# DIDV_-_Expansao_05.net
KiCad netlist of a schematic drawn in EAGLE
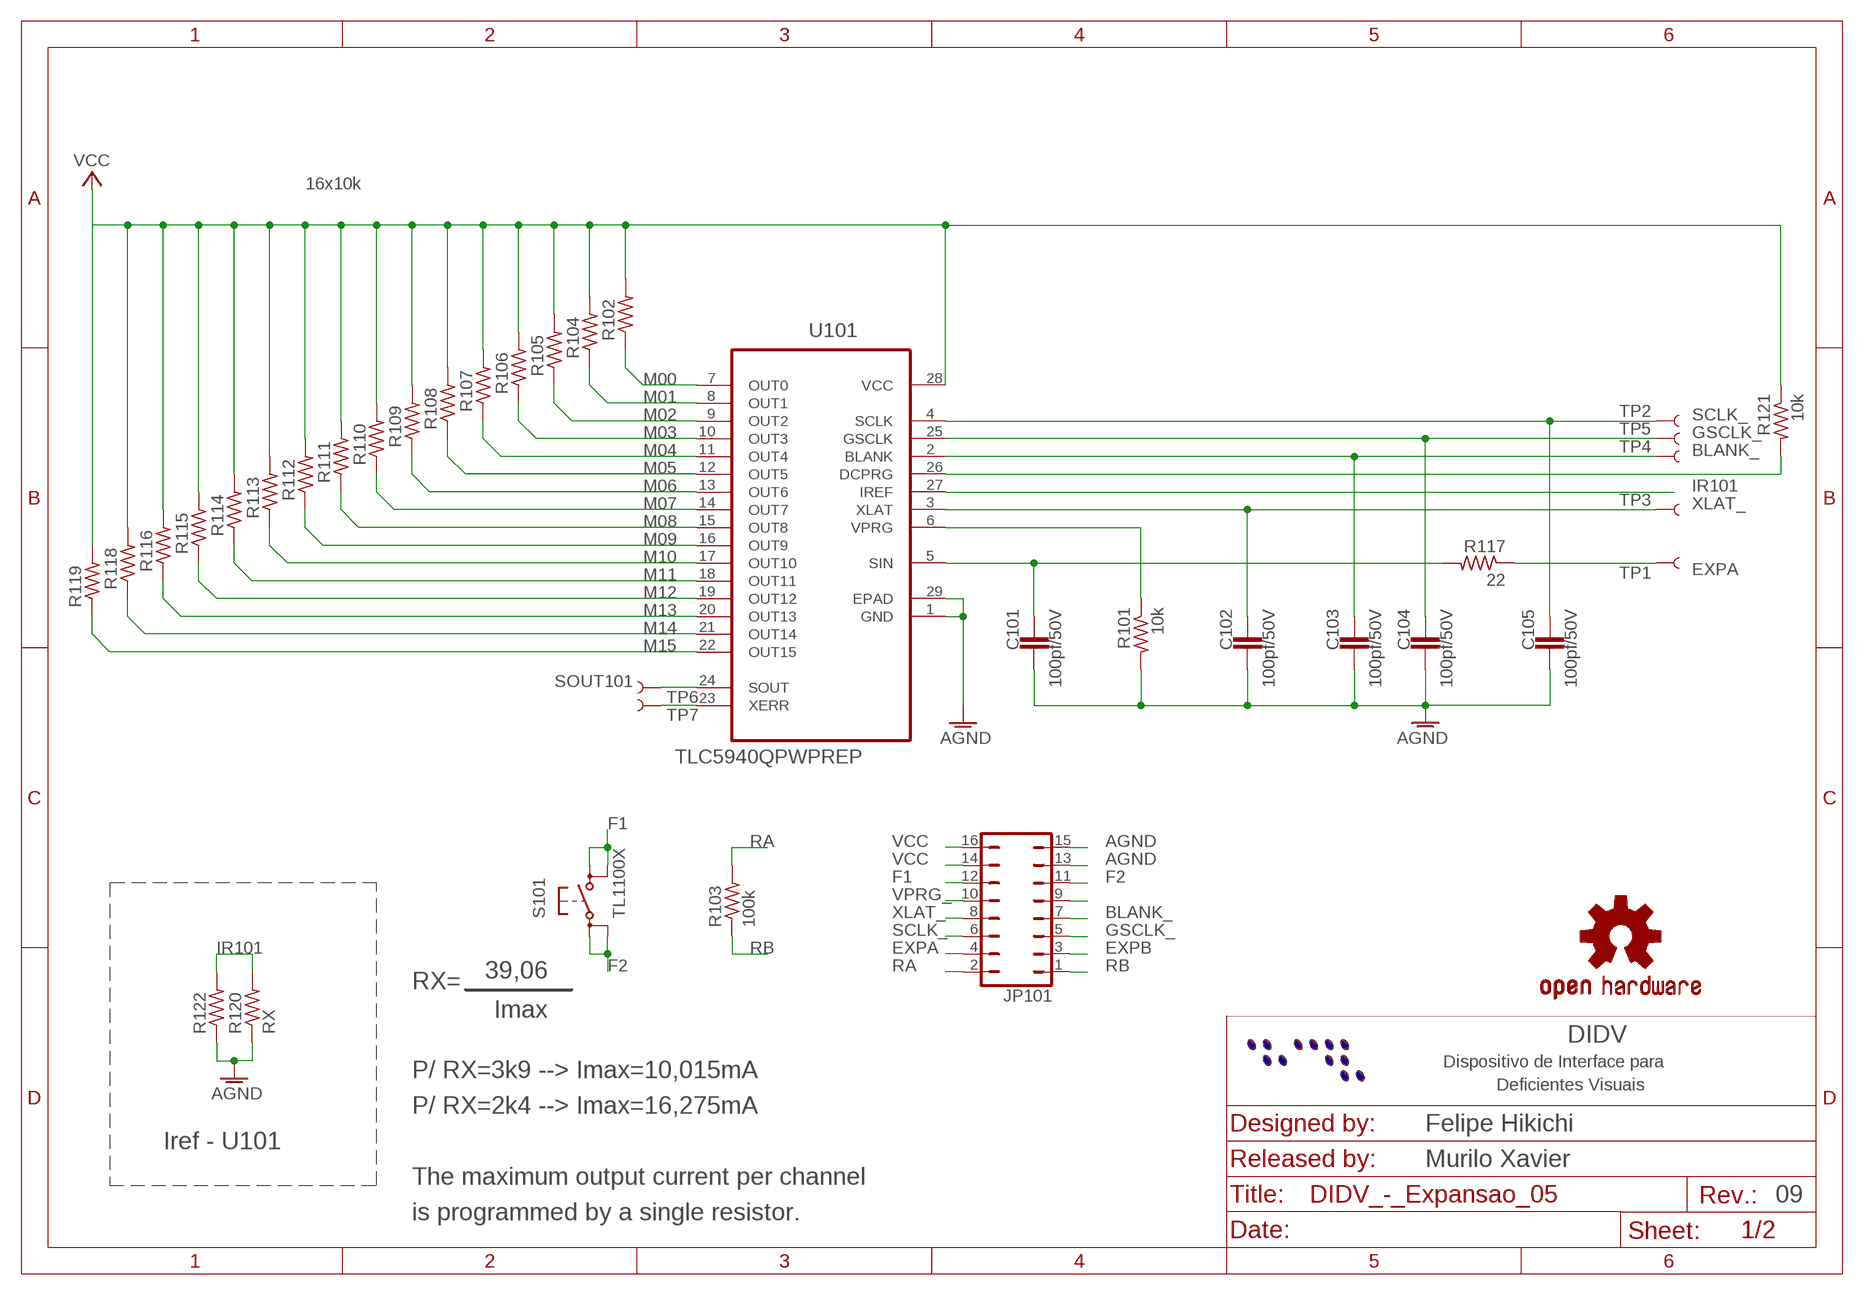
[diagram p0: schematic, sheet 1]
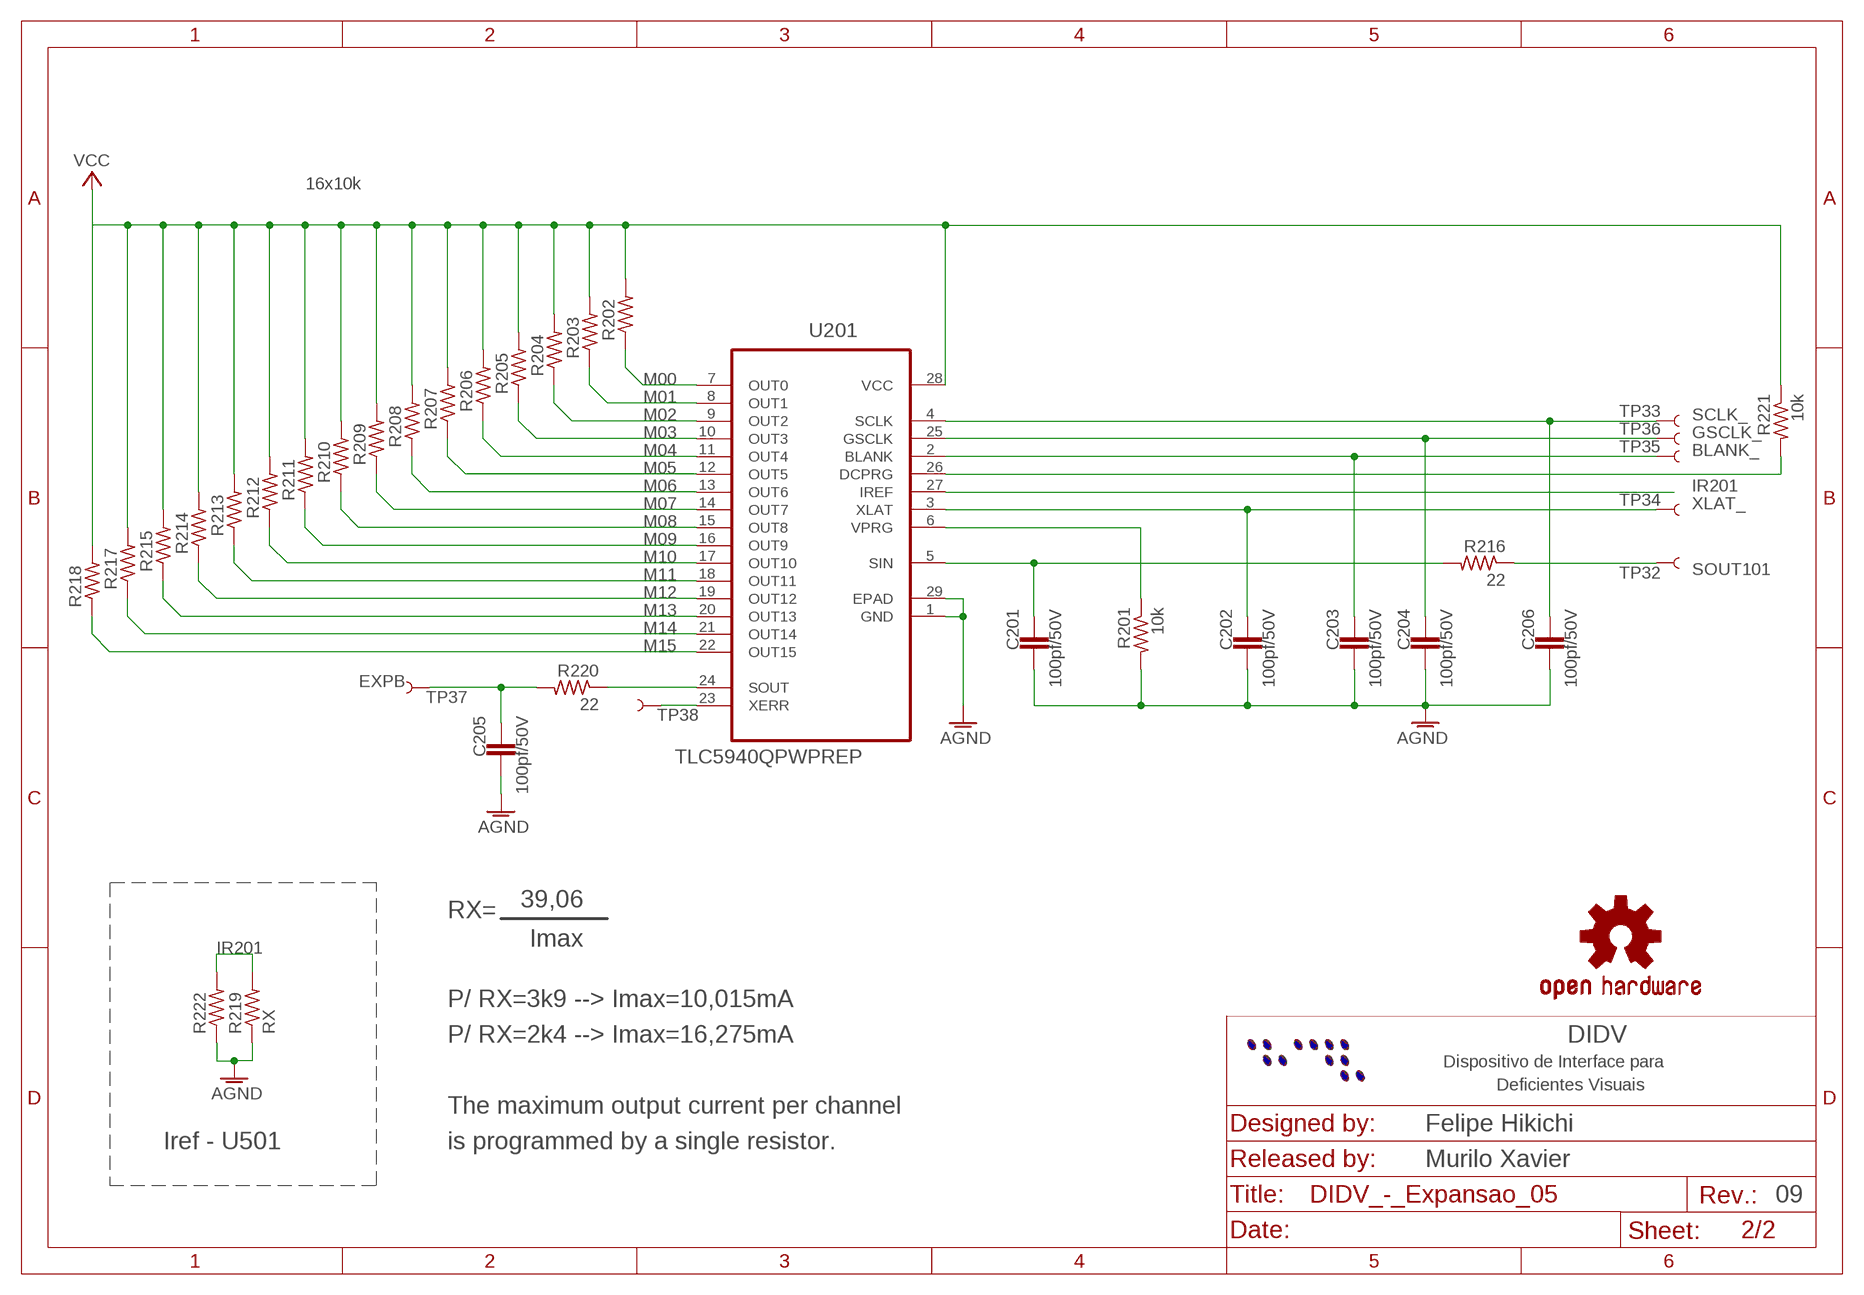
[diagram p1: schematic, sheet 2]

(export (version "E")
  (design (tool "Eeschema 10.0.6"))
  (components
    (comp (ref "C101")
      (value "100pf/50V")
      (footprint "eagle-import:C0603K")
      (libsource (lib "eagle-import") (part "C-EUC0603K"))
    )
    (comp (ref "C102")
      (value "100pf/50V")
      (footprint "eagle-import:C0603K")
      (libsource (lib "eagle-import") (part "C-EUC0603K"))
    )
    (comp (ref "C103")
      (value "100pf/50V")
      (footprint "eagle-import:C0603K")
      (libsource (lib "eagle-import") (part "C-EUC0603K"))
    )
    (comp (ref "C104")
      (value "100pf/50V")
      (footprint "eagle-import:C0603K")
      (libsource (lib "eagle-import") (part "C-EUC0603K"))
    )
    (comp (ref "C105")
      (value "100pf/50V")
      (footprint "eagle-import:C0603K")
      (libsource (lib "eagle-import") (part "C-EUC0603K"))
    )
    (comp (ref "JP101")
      (value "JP8Q")
      (footprint "eagle-import:JP8Q")
      (libsource (lib "eagle-import") (part "JP8Q"))
    )
    (comp (ref "LOGO101")
      (value "OSHW-LOGOM")
      (footprint "eagle-import:OSHW-LOGO-M")
      (libsource (lib "eagle-import") (part "OSHW-LOGOM"))
    )
    (comp (ref "R101")
      (value "10k")
      (footprint "eagle-import:R0603")
      (libsource (lib "eagle-import") (part "R-US_R0603"))
    )
    (comp (ref "R102")
      (value "R-US_R0805")
      (footprint "eagle-import:R0805")
      (libsource (lib "eagle-import") (part "R-US_R0805"))
    )
    (comp (ref "R103")
      (value "100k")
      (footprint "eagle-import:R0805")
      (libsource (lib "eagle-import") (part "R-US_R0805"))
    )
    (comp (ref "R104")
      (value "R-US_R0805")
      (footprint "eagle-import:R0805")
      (libsource (lib "eagle-import") (part "R-US_R0805"))
    )
    (comp (ref "R105")
      (value "R-US_R0805")
      (footprint "eagle-import:R0805")
      (libsource (lib "eagle-import") (part "R-US_R0805"))
    )
    (comp (ref "R106")
      (value "R-US_R0805")
      (footprint "eagle-import:R0805")
      (libsource (lib "eagle-import") (part "R-US_R0805"))
    )
    (comp (ref "R107")
      (value "R-US_R0805")
      (footprint "eagle-import:R0805")
      (libsource (lib "eagle-import") (part "R-US_R0805"))
    )
    (comp (ref "R108")
      (value "R-US_R0805")
      (footprint "eagle-import:R0805")
      (libsource (lib "eagle-import") (part "R-US_R0805"))
    )
    (comp (ref "R109")
      (value "R-US_R0805")
      (footprint "eagle-import:R0805")
      (libsource (lib "eagle-import") (part "R-US_R0805"))
    )
    (comp (ref "R110")
      (value "R-US_R0805")
      (footprint "eagle-import:R0805")
      (libsource (lib "eagle-import") (part "R-US_R0805"))
    )
    (comp (ref "R111")
      (value "R-US_R0805")
      (footprint "eagle-import:R0805")
      (libsource (lib "eagle-import") (part "R-US_R0805"))
    )
    (comp (ref "R112")
      (value "R-US_R0805")
      (footprint "eagle-import:R0805")
      (libsource (lib "eagle-import") (part "R-US_R0805"))
    )
    (comp (ref "R113")
      (value "R-US_R0805")
      (footprint "eagle-import:R0805")
      (libsource (lib "eagle-import") (part "R-US_R0805"))
    )
    (comp (ref "R114")
      (value "R-US_R0805")
      (footprint "eagle-import:R0805")
      (libsource (lib "eagle-import") (part "R-US_R0805"))
    )
    (comp (ref "R115")
      (value "R-US_R0805")
      (footprint "eagle-import:R0805")
      (libsource (lib "eagle-import") (part "R-US_R0805"))
    )
    (comp (ref "R116")
      (value "R-US_R0805")
      (footprint "eagle-import:R0805")
      (libsource (lib "eagle-import") (part "R-US_R0805"))
    )
    (comp (ref "R117")
      (value "22")
      (footprint "eagle-import:R0603")
      (libsource (lib "eagle-import") (part "R-US_R0603"))
    )
    (comp (ref "R118")
      (value "R-US_R0805")
      (footprint "eagle-import:R0805")
      (libsource (lib "eagle-import") (part "R-US_R0805"))
    )
    (comp (ref "R119")
      (value "R-US_R0805")
      (footprint "eagle-import:R0805")
      (libsource (lib "eagle-import") (part "R-US_R0805"))
    )
    (comp (ref "R120")
      (value "RX")
      (footprint "eagle-import:R0805")
      (libsource (lib "eagle-import") (part "R-US_R0805"))
    )
    (comp (ref "R121")
      (value "10k")
      (footprint "eagle-import:R0603")
      (libsource (lib "eagle-import") (part "R-US_R0603"))
    )
    (comp (ref "R122")
      (value "R-US_R0805")
      (footprint "eagle-import:R0805")
      (libsource (lib "eagle-import") (part "R-US_R0805"))
    )
    (comp (ref "S101")
      (value "TL1100X")
      (footprint "eagle-import:TL1100X")
      (libsource (lib "eagle-import") (part "TL1100X"))
    )
    (comp (ref "TP1")
      (value "TEST-POINT3X4")
      (footprint "eagle-import:PAD.03X.04")
      (libsource (lib "eagle-import") (part "TEST-POINT3X4"))
    )
    (comp (ref "TP2")
      (value "TEST-POINT3X4")
      (footprint "eagle-import:PAD.03X.04")
      (libsource (lib "eagle-import") (part "TEST-POINT3X4"))
    )
    (comp (ref "TP3")
      (value "TEST-POINT3X4")
      (footprint "eagle-import:PAD.03X.04")
      (libsource (lib "eagle-import") (part "TEST-POINT3X4"))
    )
    (comp (ref "TP4")
      (value "TEST-POINT3X4")
      (footprint "eagle-import:PAD.03X.04")
      (libsource (lib "eagle-import") (part "TEST-POINT3X4"))
    )
    (comp (ref "TP5")
      (value "TEST-POINT3X4")
      (footprint "eagle-import:PAD.03X.04")
      (libsource (lib "eagle-import") (part "TEST-POINT3X4"))
    )
    (comp (ref "TP6")
      (value "TEST-POINT3X4")
      (footprint "eagle-import:PAD.03X.04")
      (libsource (lib "eagle-import") (part "TEST-POINT3X4"))
    )
    (comp (ref "TP7")
      (value "TEST-POINT3X4")
      (footprint "eagle-import:PAD.03X.04")
      (libsource (lib "eagle-import") (part "TEST-POINT3X4"))
    )
    (comp (ref "U101")
      (value "TLC5940QPWPREP")
      (footprint "eagle-import:SOP65P640X120-29N")
      (libsource (lib "eagle-import") (part "TLC5940QPWPREP"))
    )
    (comp (ref "C201")
      (value "100pf/50V")
      (footprint "eagle-import:C0603K")
      (libsource (lib "eagle-import") (part "C-EUC0603K"))
    )
    (comp (ref "C202")
      (value "100pf/50V")
      (footprint "eagle-import:C0603K")
      (libsource (lib "eagle-import") (part "C-EUC0603K"))
    )
    (comp (ref "C203")
      (value "100pf/50V")
      (footprint "eagle-import:C0603K")
      (libsource (lib "eagle-import") (part "C-EUC0603K"))
    )
    (comp (ref "C204")
      (value "100pf/50V")
      (footprint "eagle-import:C0603K")
      (libsource (lib "eagle-import") (part "C-EUC0603K"))
    )
    (comp (ref "C205")
      (value "100pf/50V")
      (footprint "eagle-import:C0603K")
      (libsource (lib "eagle-import") (part "C-EUC0603K"))
    )
    (comp (ref "C206")
      (value "100pf/50V")
      (footprint "eagle-import:C0603K")
      (libsource (lib "eagle-import") (part "C-EUC0603K"))
    )
    (comp (ref "LOGO201")
      (value "OSHW-LOGOM")
      (footprint "eagle-import:OSHW-LOGO-M")
      (libsource (lib "eagle-import") (part "OSHW-LOGOM"))
    )
    (comp (ref "R201")
      (value "10k")
      (footprint "eagle-import:R0603")
      (libsource (lib "eagle-import") (part "R-US_R0603"))
    )
    (comp (ref "R202")
      (value "R-US_R0805")
      (footprint "eagle-import:R0805")
      (libsource (lib "eagle-import") (part "R-US_R0805"))
    )
    (comp (ref "R203")
      (value "R-US_R0805")
      (footprint "eagle-import:R0805")
      (libsource (lib "eagle-import") (part "R-US_R0805"))
    )
    (comp (ref "R204")
      (value "R-US_R0805")
      (footprint "eagle-import:R0805")
      (libsource (lib "eagle-import") (part "R-US_R0805"))
    )
    (comp (ref "R205")
      (value "R-US_R0805")
      (footprint "eagle-import:R0805")
      (libsource (lib "eagle-import") (part "R-US_R0805"))
    )
    (comp (ref "R206")
      (value "R-US_R0805")
      (footprint "eagle-import:R0805")
      (libsource (lib "eagle-import") (part "R-US_R0805"))
    )
    (comp (ref "R207")
      (value "R-US_R0805")
      (footprint "eagle-import:R0805")
      (libsource (lib "eagle-import") (part "R-US_R0805"))
    )
    (comp (ref "R208")
      (value "R-US_R0805")
      (footprint "eagle-import:R0805")
      (libsource (lib "eagle-import") (part "R-US_R0805"))
    )
    (comp (ref "R209")
      (value "R-US_R0805")
      (footprint "eagle-import:R0805")
      (libsource (lib "eagle-import") (part "R-US_R0805"))
    )
    (comp (ref "R210")
      (value "R-US_R0805")
      (footprint "eagle-import:R0805")
      (libsource (lib "eagle-import") (part "R-US_R0805"))
    )
    (comp (ref "R211")
      (value "R-US_R0805")
      (footprint "eagle-import:R0805")
      (libsource (lib "eagle-import") (part "R-US_R0805"))
    )
    (comp (ref "R212")
      (value "R-US_R0805")
      (footprint "eagle-import:R0805")
      (libsource (lib "eagle-import") (part "R-US_R0805"))
    )
    (comp (ref "R213")
      (value "R-US_R0805")
      (footprint "eagle-import:R0805")
      (libsource (lib "eagle-import") (part "R-US_R0805"))
    )
    (comp (ref "R214")
      (value "R-US_R0805")
      (footprint "eagle-import:R0805")
      (libsource (lib "eagle-import") (part "R-US_R0805"))
    )
    (comp (ref "R215")
      (value "R-US_R0805")
      (footprint "eagle-import:R0805")
      (libsource (lib "eagle-import") (part "R-US_R0805"))
    )
    (comp (ref "R216")
      (value "22")
      (footprint "eagle-import:R0603")
      (libsource (lib "eagle-import") (part "R-US_R0603"))
    )
    (comp (ref "R217")
      (value "R-US_R0805")
      (footprint "eagle-import:R0805")
      (libsource (lib "eagle-import") (part "R-US_R0805"))
    )
    (comp (ref "R218")
      (value "R-US_R0805")
      (footprint "eagle-import:R0805")
      (libsource (lib "eagle-import") (part "R-US_R0805"))
    )
    (comp (ref "R219")
      (value "RX")
      (footprint "eagle-import:R0805")
      (libsource (lib "eagle-import") (part "R-US_R0805"))
    )
    (comp (ref "R220")
      (value "22")
      (footprint "eagle-import:R0603")
      (libsource (lib "eagle-import") (part "R-US_R0603"))
    )
    (comp (ref "R221")
      (value "10k")
      (footprint "eagle-import:R0603")
      (libsource (lib "eagle-import") (part "R-US_R0603"))
    )
    (comp (ref "R222")
      (value "R-US_R0805")
      (footprint "eagle-import:R0805")
      (libsource (lib "eagle-import") (part "R-US_R0805"))
    )
    (comp (ref "TP32")
      (value "TEST-POINT3X4")
      (footprint "eagle-import:PAD.03X.04")
      (libsource (lib "eagle-import") (part "TEST-POINT3X4"))
    )
    (comp (ref "TP33")
      (value "TEST-POINT3X4")
      (footprint "eagle-import:PAD.03X.04")
      (libsource (lib "eagle-import") (part "TEST-POINT3X4"))
    )
    (comp (ref "TP34")
      (value "TEST-POINT3X4")
      (footprint "eagle-import:PAD.03X.04")
      (libsource (lib "eagle-import") (part "TEST-POINT3X4"))
    )
    (comp (ref "TP35")
      (value "TEST-POINT3X4")
      (footprint "eagle-import:PAD.03X.04")
      (libsource (lib "eagle-import") (part "TEST-POINT3X4"))
    )
    (comp (ref "TP36")
      (value "TEST-POINT3X4")
      (footprint "eagle-import:PAD.03X.04")
      (libsource (lib "eagle-import") (part "TEST-POINT3X4"))
    )
    (comp (ref "TP37")
      (value "TEST-POINT3X4")
      (footprint "eagle-import:PAD.03X.04")
      (libsource (lib "eagle-import") (part "TEST-POINT3X4"))
    )
    (comp (ref "TP38")
      (value "TEST-POINT3X4")
      (footprint "eagle-import:PAD.03X.04")
      (libsource (lib "eagle-import") (part "TEST-POINT3X4"))
    )
    (comp (ref "U201")
      (value "TLC5940QPWPREP")
      (footprint "eagle-import:SOP65P640X120-29N")
      (libsource (lib "eagle-import") (part "TLC5940QPWPREP"))
    )
  )
  (nets
    (net (code "1") (name "AGND") (class "Default")
      (node (ref "C101") (pin "1") (pinfunction "1_1") (pintype "passive"))
      (node (ref "C102") (pin "1") (pinfunction "1_1") (pintype "passive"))
      (node (ref "C103") (pin "1") (pinfunction "1_1") (pintype "passive"))
      (node (ref "C104") (pin "1") (pinfunction "1_1") (pintype "passive"))
      (node (ref "C105") (pin "1") (pinfunction "1_1") (pintype "passive"))
      (node (ref "C201") (pin "1") (pinfunction "1_1") (pintype "passive"))
      (node (ref "C202") (pin "1") (pinfunction "1_1") (pintype "passive"))
      (node (ref "C203") (pin "1") (pinfunction "1_1") (pintype "passive"))
      (node (ref "C204") (pin "1") (pinfunction "1_1") (pintype "passive"))
      (node (ref "C205") (pin "1") (pinfunction "1_1") (pintype "passive"))
      (node (ref "C206") (pin "1") (pinfunction "1_1") (pintype "passive"))
      (node (ref "JP101") (pin "13") (pinfunction "13_13") (pintype "passive"))
      (node (ref "JP101") (pin "15") (pinfunction "15_15") (pintype "passive"))
      (node (ref "R101") (pin "2") (pinfunction "2_2") (pintype "passive"))
      (node (ref "R120") (pin "1") (pinfunction "1_1") (pintype "passive"))
      (node (ref "R122") (pin "1") (pinfunction "1_1") (pintype "passive"))
      (node (ref "R201") (pin "2") (pinfunction "2_2") (pintype "passive"))
      (node (ref "R219") (pin "1") (pinfunction "1_1") (pintype "passive"))
      (node (ref "R222") (pin "1") (pinfunction "1_1") (pintype "passive"))
      (node (ref "U101") (pin "1") (pinfunction "GND_1") (pintype "passive"))
      (node (ref "U101") (pin "29") (pinfunction "EPAD_29") (pintype "passive"))
      (node (ref "U201") (pin "1") (pinfunction "GND_1") (pintype "passive"))
      (node (ref "U201") (pin "29") (pinfunction "EPAD_29") (pintype "passive"))
    )
    (net (code "2") (name "BLANK_") (class "Default")
      (node (ref "C103") (pin "2") (pinfunction "2_2") (pintype "passive"))
      (node (ref "C203") (pin "2") (pinfunction "2_2") (pintype "passive"))
      (node (ref "JP101") (pin "7") (pinfunction "7_7") (pintype "passive"))
      (node (ref "TP35") (pin "P$1") (pinfunction "1_P$1") (pintype "bidirectional"))
      (node (ref "TP4") (pin "P$1") (pinfunction "1_P$1") (pintype "bidirectional"))
      (node (ref "U101") (pin "2") (pinfunction "BLANK_2") (pintype "input"))
      (node (ref "U201") (pin "2") (pinfunction "BLANK_2") (pintype "input"))
    )
    (net (code "3") (name "EXPA") (class "Default")
      (node (ref "JP101") (pin "4") (pinfunction "4_4") (pintype "passive"))
      (node (ref "R117") (pin "1") (pinfunction "1_1") (pintype "passive"))
      (node (ref "TP1") (pin "P$1") (pinfunction "1_P$1") (pintype "bidirectional"))
    )
    (net (code "4") (name "EXPB") (class "Default")
      (node (ref "C205") (pin "2") (pinfunction "2_2") (pintype "passive"))
      (node (ref "JP101") (pin "3") (pinfunction "3_3") (pintype "passive"))
      (node (ref "R220") (pin "2") (pinfunction "2_2") (pintype "passive"))
      (node (ref "TP37") (pin "P$1") (pinfunction "1_P$1") (pintype "bidirectional"))
    )
    (net (code "5") (name "F1") (class "Default")
      (node (ref "JP101") (pin "12") (pinfunction "12_12") (pintype "passive"))
      (node (ref "S101") (pin "3") (pinfunction "S_3") (pintype "passive"))
      (node (ref "S101") (pin "4") (pinfunction "S1_4") (pintype "passive"))
    )
    (net (code "6") (name "F2") (class "Default")
      (node (ref "JP101") (pin "11") (pinfunction "11_11") (pintype "passive"))
      (node (ref "S101") (pin "1") (pinfunction "P_1") (pintype "passive"))
      (node (ref "S101") (pin "2") (pinfunction "P1_2") (pintype "passive"))
    )
    (net (code "7") (name "GSCLK_") (class "Default")
      (node (ref "C104") (pin "2") (pinfunction "2_2") (pintype "passive"))
      (node (ref "C204") (pin "2") (pinfunction "2_2") (pintype "passive"))
      (node (ref "JP101") (pin "5") (pinfunction "5_5") (pintype "passive"))
      (node (ref "TP36") (pin "P$1") (pinfunction "1_P$1") (pintype "bidirectional"))
      (node (ref "TP5") (pin "P$1") (pinfunction "1_P$1") (pintype "bidirectional"))
      (node (ref "U101") (pin "25") (pinfunction "GSCLK_25") (pintype "input"))
      (node (ref "U201") (pin "25") (pinfunction "GSCLK_25") (pintype "input"))
    )
    (net (code "8") (name "IR101") (class "Default")
      (node (ref "R120") (pin "2") (pinfunction "2_2") (pintype "passive"))
      (node (ref "R122") (pin "2") (pinfunction "2_2") (pintype "passive"))
      (node (ref "U101") (pin "27") (pinfunction "IREF_27") (pintype "input"))
    )
    (net (code "9") (name "IR201") (class "Default")
      (node (ref "R219") (pin "2") (pinfunction "2_2") (pintype "passive"))
      (node (ref "R222") (pin "2") (pinfunction "2_2") (pintype "passive"))
      (node (ref "U201") (pin "27") (pinfunction "IREF_27") (pintype "input"))
    )
    (net (code "10") (name "M00") (class "Default")
      (node (ref "R102") (pin "1") (pinfunction "1_1") (pintype "passive"))
      (node (ref "R202") (pin "1") (pinfunction "1_1") (pintype "passive"))
      (node (ref "U101") (pin "7") (pinfunction "OUT0_7") (pintype "output"))
      (node (ref "U201") (pin "7") (pinfunction "OUT0_7") (pintype "output"))
    )
    (net (code "11") (name "M01") (class "Default")
      (node (ref "R104") (pin "1") (pinfunction "1_1") (pintype "passive"))
      (node (ref "R203") (pin "1") (pinfunction "1_1") (pintype "passive"))
      (node (ref "U101") (pin "8") (pinfunction "OUT1_8") (pintype "output"))
      (node (ref "U201") (pin "8") (pinfunction "OUT1_8") (pintype "output"))
    )
    (net (code "12") (name "M02") (class "Default")
      (node (ref "R105") (pin "1") (pinfunction "1_1") (pintype "passive"))
      (node (ref "R204") (pin "1") (pinfunction "1_1") (pintype "passive"))
      (node (ref "U101") (pin "9") (pinfunction "OUT2_9") (pintype "output"))
      (node (ref "U201") (pin "9") (pinfunction "OUT2_9") (pintype "output"))
    )
    (net (code "13") (name "M03") (class "Default")
      (node (ref "R106") (pin "1") (pinfunction "1_1") (pintype "passive"))
      (node (ref "R205") (pin "1") (pinfunction "1_1") (pintype "passive"))
      (node (ref "U101") (pin "10") (pinfunction "OUT3_10") (pintype "output"))
      (node (ref "U201") (pin "10") (pinfunction "OUT3_10") (pintype "output"))
    )
    (net (code "14") (name "M04") (class "Default")
      (node (ref "R107") (pin "1") (pinfunction "1_1") (pintype "passive"))
      (node (ref "R206") (pin "1") (pinfunction "1_1") (pintype "passive"))
      (node (ref "U101") (pin "11") (pinfunction "OUT4_11") (pintype "output"))
      (node (ref "U201") (pin "11") (pinfunction "OUT4_11") (pintype "output"))
    )
    (net (code "15") (name "M05") (class "Default")
      (node (ref "R108") (pin "1") (pinfunction "1_1") (pintype "passive"))
      (node (ref "R207") (pin "1") (pinfunction "1_1") (pintype "passive"))
      (node (ref "U101") (pin "12") (pinfunction "OUT5_12") (pintype "output"))
      (node (ref "U201") (pin "12") (pinfunction "OUT5_12") (pintype "output"))
    )
    (net (code "16") (name "M06") (class "Default")
      (node (ref "R109") (pin "1") (pinfunction "1_1") (pintype "passive"))
      (node (ref "R208") (pin "1") (pinfunction "1_1") (pintype "passive"))
      (node (ref "U101") (pin "13") (pinfunction "OUT6_13") (pintype "output"))
      (node (ref "U201") (pin "13") (pinfunction "OUT6_13") (pintype "output"))
    )
    (net (code "17") (name "M07") (class "Default")
      (node (ref "R110") (pin "1") (pinfunction "1_1") (pintype "passive"))
      (node (ref "R209") (pin "1") (pinfunction "1_1") (pintype "passive"))
      (node (ref "U101") (pin "14") (pinfunction "OUT7_14") (pintype "output"))
      (node (ref "U201") (pin "14") (pinfunction "OUT7_14") (pintype "output"))
    )
    (net (code "18") (name "M08") (class "Default")
      (node (ref "R111") (pin "1") (pinfunction "1_1") (pintype "passive"))
      (node (ref "R210") (pin "1") (pinfunction "1_1") (pintype "passive"))
      (node (ref "U101") (pin "15") (pinfunction "OUT8_15") (pintype "output"))
      (node (ref "U201") (pin "15") (pinfunction "OUT8_15") (pintype "output"))
    )
    (net (code "19") (name "M09") (class "Default")
      (node (ref "R112") (pin "1") (pinfunction "1_1") (pintype "passive"))
      (node (ref "R211") (pin "1") (pinfunction "1_1") (pintype "passive"))
      (node (ref "U101") (pin "16") (pinfunction "OUT9_16") (pintype "output"))
      (node (ref "U201") (pin "16") (pinfunction "OUT9_16") (pintype "output"))
    )
    (net (code "20") (name "M10") (class "Default")
      (node (ref "R113") (pin "1") (pinfunction "1_1") (pintype "passive"))
      (node (ref "R212") (pin "1") (pinfunction "1_1") (pintype "passive"))
      (node (ref "U101") (pin "17") (pinfunction "OUT10_17") (pintype "output"))
      (node (ref "U201") (pin "17") (pinfunction "OUT10_17") (pintype "output"))
    )
    (net (code "21") (name "M11") (class "Default")
      (node (ref "R114") (pin "1") (pinfunction "1_1") (pintype "passive"))
      (node (ref "R213") (pin "1") (pinfunction "1_1") (pintype "passive"))
      (node (ref "U101") (pin "18") (pinfunction "OUT11_18") (pintype "output"))
      (node (ref "U201") (pin "18") (pinfunction "OUT11_18") (pintype "output"))
    )
    (net (code "22") (name "M12") (class "Default")
      (node (ref "R115") (pin "1") (pinfunction "1_1") (pintype "passive"))
      (node (ref "R214") (pin "1") (pinfunction "1_1") (pintype "passive"))
      (node (ref "U101") (pin "19") (pinfunction "OUT12_19") (pintype "output"))
      (node (ref "U201") (pin "19") (pinfunction "OUT12_19") (pintype "output"))
    )
    (net (code "23") (name "M13") (class "Default")
      (node (ref "R116") (pin "1") (pinfunction "1_1") (pintype "passive"))
      (node (ref "R215") (pin "1") (pinfunction "1_1") (pintype "passive"))
      (node (ref "U101") (pin "20") (pinfunction "OUT13_20") (pintype "output"))
      (node (ref "U201") (pin "20") (pinfunction "OUT13_20") (pintype "output"))
    )
    (net (code "24") (name "M14") (class "Default")
      (node (ref "R118") (pin "1") (pinfunction "1_1") (pintype "passive"))
      (node (ref "R217") (pin "1") (pinfunction "1_1") (pintype "passive"))
      (node (ref "U101") (pin "21") (pinfunction "OUT14_21") (pintype "output"))
      (node (ref "U201") (pin "21") (pinfunction "OUT14_21") (pintype "output"))
    )
    (net (code "25") (name "M15") (class "Default")
      (node (ref "R119") (pin "1") (pinfunction "1_1") (pintype "passive"))
      (node (ref "R218") (pin "1") (pinfunction "1_1") (pintype "passive"))
      (node (ref "U101") (pin "22") (pinfunction "OUT15_22") (pintype "output"))
      (node (ref "U201") (pin "22") (pinfunction "OUT15_22") (pintype "output"))
    )
    (net (code "26") (name "Net-(TP7-1)") (class "Default")
      (node (ref "TP7") (pin "P$1") (pinfunction "1_P$1") (pintype "bidirectional"))
      (node (ref "U101") (pin "23") (pinfunction "XERR_23") (pintype "output"))
    )
    (net (code "27") (name "Net-(TP38-1)") (class "Default")
      (node (ref "TP38") (pin "P$1") (pinfunction "1_P$1") (pintype "bidirectional"))
      (node (ref "U201") (pin "23") (pinfunction "XERR_23") (pintype "output"))
    )
    (net (code "28") (name "Net-(U101-DCPRG)") (class "Default")
      (node (ref "R121") (pin "2") (pinfunction "2_2") (pintype "passive"))
      (node (ref "U101") (pin "26") (pinfunction "DCPRG_26") (pintype "input"))
    )
    (net (code "29") (name "Net-(U101-SIN)") (class "Default")
      (node (ref "C101") (pin "2") (pinfunction "2_2") (pintype "passive"))
      (node (ref "R117") (pin "2") (pinfunction "2_2") (pintype "passive"))
      (node (ref "U101") (pin "5") (pinfunction "SIN_5") (pintype "input"))
    )
    (net (code "30") (name "Net-(U201-DCPRG)") (class "Default")
      (node (ref "R221") (pin "2") (pinfunction "2_2") (pintype "passive"))
      (node (ref "U201") (pin "26") (pinfunction "DCPRG_26") (pintype "input"))
    )
    (net (code "31") (name "Net-(U201-SIN)") (class "Default")
      (node (ref "C201") (pin "2") (pinfunction "2_2") (pintype "passive"))
      (node (ref "R216") (pin "2") (pinfunction "2_2") (pintype "passive"))
      (node (ref "U201") (pin "5") (pinfunction "SIN_5") (pintype "input"))
    )
    (net (code "32") (name "Net-(U201-SOUT)") (class "Default")
      (node (ref "R220") (pin "1") (pinfunction "1_1") (pintype "passive"))
      (node (ref "U201") (pin "24") (pinfunction "SOUT_24") (pintype "output"))
    )
    (net (code "33") (name "RA") (class "Default")
      (node (ref "JP101") (pin "2") (pinfunction "2_2") (pintype "passive"))
      (node (ref "R103") (pin "2") (pinfunction "2_2") (pintype "passive"))
    )
    (net (code "34") (name "RB") (class "Default")
      (node (ref "JP101") (pin "1") (pinfunction "1_1") (pintype "passive"))
      (node (ref "R103") (pin "1") (pinfunction "1_1") (pintype "passive"))
    )
    (net (code "35") (name "SCLK_") (class "Default")
      (node (ref "C105") (pin "2") (pinfunction "2_2") (pintype "passive"))
      (node (ref "C206") (pin "2") (pinfunction "2_2") (pintype "passive"))
      (node (ref "JP101") (pin "6") (pinfunction "6_6") (pintype "passive"))
      (node (ref "TP2") (pin "P$1") (pinfunction "1_P$1") (pintype "bidirectional"))
      (node (ref "TP33") (pin "P$1") (pinfunction "1_P$1") (pintype "bidirectional"))
      (node (ref "U101") (pin "4") (pinfunction "SCLK_4") (pintype "input"))
      (node (ref "U201") (pin "4") (pinfunction "SCLK_4") (pintype "input"))
    )
    (net (code "36") (name "SOUT101") (class "Default")
      (node (ref "R216") (pin "1") (pinfunction "1_1") (pintype "passive"))
      (node (ref "TP32") (pin "P$1") (pinfunction "1_P$1") (pintype "bidirectional"))
      (node (ref "TP6") (pin "P$1") (pinfunction "1_P$1") (pintype "bidirectional"))
      (node (ref "U101") (pin "24") (pinfunction "SOUT_24") (pintype "output"))
    )
    (net (code "37") (name "VCC") (class "Default")
      (node (ref "JP101") (pin "14") (pinfunction "14_14") (pintype "passive"))
      (node (ref "JP101") (pin "16") (pinfunction "16_16") (pintype "passive"))
      (node (ref "R102") (pin "2") (pinfunction "2_2") (pintype "passive"))
      (node (ref "R104") (pin "2") (pinfunction "2_2") (pintype "passive"))
      (node (ref "R105") (pin "2") (pinfunction "2_2") (pintype "passive"))
      (node (ref "R106") (pin "2") (pinfunction "2_2") (pintype "passive"))
      (node (ref "R107") (pin "2") (pinfunction "2_2") (pintype "passive"))
      (node (ref "R108") (pin "2") (pinfunction "2_2") (pintype "passive"))
      (node (ref "R109") (pin "2") (pinfunction "2_2") (pintype "passive"))
      (node (ref "R110") (pin "2") (pinfunction "2_2") (pintype "passive"))
      (node (ref "R111") (pin "2") (pinfunction "2_2") (pintype "passive"))
      (node (ref "R112") (pin "2") (pinfunction "2_2") (pintype "passive"))
      (node (ref "R113") (pin "2") (pinfunction "2_2") (pintype "passive"))
      (node (ref "R114") (pin "2") (pinfunction "2_2") (pintype "passive"))
      (node (ref "R115") (pin "2") (pinfunction "2_2") (pintype "passive"))
      (node (ref "R116") (pin "2") (pinfunction "2_2") (pintype "passive"))
      (node (ref "R118") (pin "2") (pinfunction "2_2") (pintype "passive"))
      (node (ref "R119") (pin "2") (pinfunction "2_2") (pintype "passive"))
      (node (ref "R121") (pin "1") (pinfunction "1_1") (pintype "passive"))
      (node (ref "R202") (pin "2") (pinfunction "2_2") (pintype "passive"))
      (node (ref "R203") (pin "2") (pinfunction "2_2") (pintype "passive"))
      (node (ref "R204") (pin "2") (pinfunction "2_2") (pintype "passive"))
      (node (ref "R205") (pin "2") (pinfunction "2_2") (pintype "passive"))
      (node (ref "R206") (pin "2") (pinfunction "2_2") (pintype "passive"))
      (node (ref "R207") (pin "2") (pinfunction "2_2") (pintype "passive"))
      (node (ref "R208") (pin "2") (pinfunction "2_2") (pintype "passive"))
      (node (ref "R209") (pin "2") (pinfunction "2_2") (pintype "passive"))
      (node (ref "R210") (pin "2") (pinfunction "2_2") (pintype "passive"))
      (node (ref "R211") (pin "2") (pinfunction "2_2") (pintype "passive"))
      (node (ref "R212") (pin "2") (pinfunction "2_2") (pintype "passive"))
      (node (ref "R213") (pin "2") (pinfunction "2_2") (pintype "passive"))
      (node (ref "R214") (pin "2") (pinfunction "2_2") (pintype "passive"))
      (node (ref "R215") (pin "2") (pinfunction "2_2") (pintype "passive"))
      (node (ref "R217") (pin "2") (pinfunction "2_2") (pintype "passive"))
      (node (ref "R218") (pin "2") (pinfunction "2_2") (pintype "passive"))
      (node (ref "R221") (pin "1") (pinfunction "1_1") (pintype "passive"))
      (node (ref "U101") (pin "28") (pinfunction "VCC_28") (pintype "power_in"))
      (node (ref "U201") (pin "28") (pinfunction "VCC_28") (pintype "power_in"))
    )
    (net (code "38") (name "VPRG_") (class "Default")
      (node (ref "JP101") (pin "10") (pinfunction "10_10") (pintype "passive"))
      (node (ref "R101") (pin "1") (pinfunction "1_1") (pintype "passive"))
      (node (ref "R201") (pin "1") (pinfunction "1_1") (pintype "passive"))
      (node (ref "U101") (pin "6") (pinfunction "VPRG_6") (pintype "input"))
      (node (ref "U201") (pin "6") (pinfunction "VPRG_6") (pintype "input"))
    )
    (net (code "39") (name "XLAT_") (class "Default")
      (node (ref "C102") (pin "2") (pinfunction "2_2") (pintype "passive"))
      (node (ref "C202") (pin "2") (pinfunction "2_2") (pintype "passive"))
      (node (ref "JP101") (pin "8") (pinfunction "8_8") (pintype "passive"))
      (node (ref "TP3") (pin "P$1") (pinfunction "1_P$1") (pintype "bidirectional"))
      (node (ref "TP34") (pin "P$1") (pinfunction "1_P$1") (pintype "bidirectional"))
      (node (ref "U101") (pin "3") (pinfunction "XLAT_3") (pintype "input"))
      (node (ref "U201") (pin "3") (pinfunction "XLAT_3") (pintype "input"))
    )
    (net (code "40") (name "unconnected-(JP101-Pad9)") (class "Default")
      (node (ref "JP101") (pin "9") (pinfunction "9_9") (pintype "passive"))
    )
  )
)
